# ActuatorController.net
KiCad netlist of a schematic drawn in EAGLE
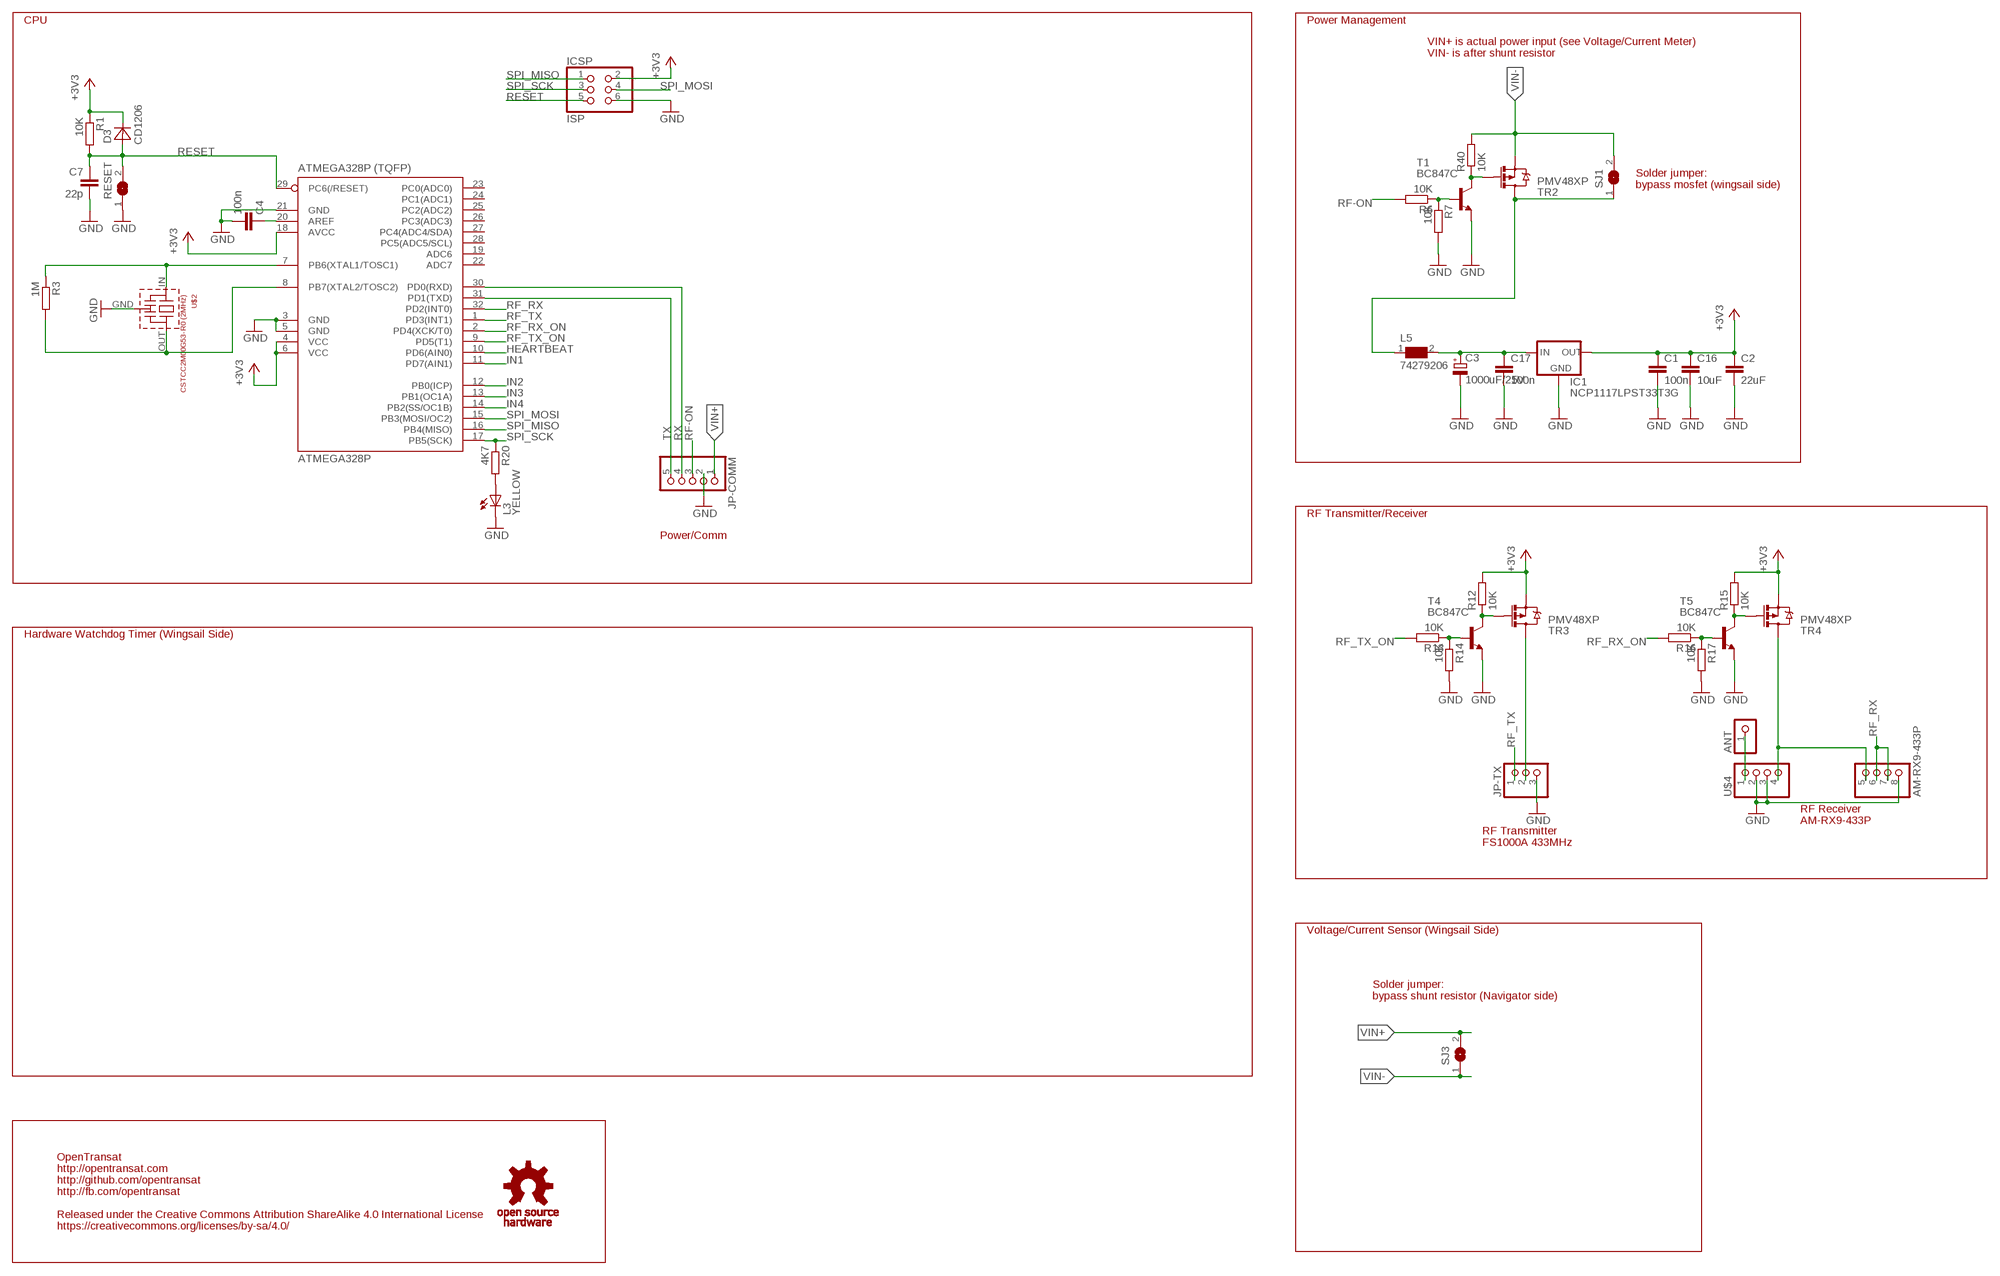
[diagram p0: schematic, sheet 1]

(export (version "E")
  (design (tool "Eeschema 10.0.6"))
  (components
    (comp (ref "ANT")
      (value "PINHD-1X1")
      (footprint "eagle-import:1X01")
      (libsource (lib "eagle-import") (part "PINHD-1X1"))
    )
    (comp (ref "ATMEGA328P")
      (value "ATMEGA328P (TQFP)")
      (footprint "eagle-import:TQFP32-08")
      (fields (field (name "MPN") "ATMEGA8-16AU"))
      (libsource (lib "eagle-import") (part "MEGA8-AI"))
    )
    (comp (ref "C1")
      (value "100n")
      (footprint "eagle-import:C0603")
      (libsource (lib "eagle-import") (part "C-EUC0603"))
    )
    (comp (ref "C2")
      (value "22uF")
      (footprint "eagle-import:C1210")
      (libsource (lib "eagle-import") (part "C-EUC1210"))
    )
    (comp (ref "C3")
      (value "1000uF/25V")
      (footprint "eagle-import:E5-10,5")
      (libsource (lib "eagle-import") (part "CPOL-EUE5-10.5"))
    )
    (comp (ref "C4")
      (value "100n")
      (footprint "eagle-import:C0603")
      (libsource (lib "eagle-import") (part "C-EUC0603"))
    )
    (comp (ref "C7")
      (value "22p")
      (footprint "eagle-import:C0603")
      (libsource (lib "eagle-import") (part "C-EUC0603"))
    )
    (comp (ref "C16")
      (value "10uF")
      (footprint "eagle-import:C1206")
      (libsource (lib "eagle-import") (part "C-EUC1206"))
    )
    (comp (ref "C17")
      (value "100n")
      (footprint "eagle-import:C0603")
      (libsource (lib "eagle-import") (part "C-EUC0603"))
    )
    (comp (ref "D3")
      (value "CD1206")
      (footprint "eagle-import:R1206")
      (libsource (lib "eagle-import") (part "CD1206"))
    )
    (comp (ref "IC1")
      (value "NCP1117LPST33T3G")
      (footprint "eagle-import:SOT223")
      (fields (field (name "MF") "Texas Instruments") (field (name "MPN") "LM1117MP-3.3"))
      (libsource (lib "eagle-import") (part "LM1117?-MP3.3"))
    )
    (comp (ref "ICSP")
      (value "ISP")
      (footprint "eagle-import:2X03")
      (libsource (lib "eagle-import") (part "PINHD-2X3"))
    )
    (comp (ref "JP-COMM")
      (value "PINHD-1X5/90")
      (footprint "eagle-import:1X05_90")
      (libsource (lib "eagle-import") (part "PINHD-1X5/90"))
    )
    (comp (ref "JP-TX")
      (value "PINHD-1X3")
      (footprint "eagle-import:1X03")
      (libsource (lib "eagle-import") (part "PINHD-1X3"))
    )
    (comp (ref "L3")
      (value "YELLOW")
      (footprint "eagle-import:CHIPLED_0805")
      (libsource (lib "eagle-import") (part "LEDCHIPLED_0805"))
    )
    (comp (ref "L5")
      (value "74279206")
      (footprint "eagle-import:0805")
      (libsource (lib "eagle-import") (part "WE-CBF_0805"))
    )
    (comp (ref "R1")
      (value "10K")
      (footprint "eagle-import:R0603")
      (libsource (lib "eagle-import") (part "R-EU_R0603"))
    )
    (comp (ref "R3")
      (value "1M")
      (footprint "eagle-import:R0603")
      (libsource (lib "eagle-import") (part "R-EU_R0603"))
    )
    (comp (ref "R6")
      (value "10K")
      (footprint "eagle-import:R0603")
      (libsource (lib "eagle-import") (part "R-EU_R0603"))
    )
    (comp (ref "R7")
      (value "10K")
      (footprint "eagle-import:R0603")
      (libsource (lib "eagle-import") (part "R-EU_R0603"))
    )
    (comp (ref "R12")
      (value "10K")
      (footprint "eagle-import:R0603")
      (libsource (lib "eagle-import") (part "R-EU_R0603"))
    )
    (comp (ref "R13")
      (value "10K")
      (footprint "eagle-import:R0603")
      (libsource (lib "eagle-import") (part "R-EU_R0603"))
    )
    (comp (ref "R14")
      (value "10K")
      (footprint "eagle-import:R0603")
      (libsource (lib "eagle-import") (part "R-EU_R0603"))
    )
    (comp (ref "R15")
      (value "10K")
      (footprint "eagle-import:R0603")
      (libsource (lib "eagle-import") (part "R-EU_R0603"))
    )
    (comp (ref "R16")
      (value "10K")
      (footprint "eagle-import:R0603")
      (libsource (lib "eagle-import") (part "R-EU_R0603"))
    )
    (comp (ref "R17")
      (value "10K")
      (footprint "eagle-import:R0603")
      (libsource (lib "eagle-import") (part "R-EU_R0603"))
    )
    (comp (ref "R20")
      (value "4K7")
      (footprint "eagle-import:R0603")
      (libsource (lib "eagle-import") (part "R-EU_R0603"))
    )
    (comp (ref "R40")
      (value "10K")
      (footprint "eagle-import:R0603")
      (libsource (lib "eagle-import") (part "R-EU_R0603"))
    )
    (comp (ref "RESET")
      (value "SJW")
      (footprint "eagle-import:SJW")
      (libsource (lib "eagle-import") (part "SJW"))
    )
    (comp (ref "SJ1") (value "SJ") (footprint "eagle-import:SJ") (libsource (lib "eagle-import") (part "SJ")))
    (comp (ref "SJ3") (value "SJ") (footprint "eagle-import:SJ") (libsource (lib "eagle-import") (part "SJ")))
    (comp (ref "T1")
      (value "BC847C")
      (footprint "eagle-import:SOT23")
      (libsource (lib "eagle-import") (part "BC847"))
    )
    (comp (ref "T4")
      (value "BC847C")
      (footprint "eagle-import:SOT23")
      (libsource (lib "eagle-import") (part "BC847"))
    )
    (comp (ref "T5")
      (value "BC847C")
      (footprint "eagle-import:SOT23")
      (libsource (lib "eagle-import") (part "BC847"))
    )
    (comp (ref "TR2")
      (value "PMV48XP")
      (footprint "eagle-import:SOT23-3")
      (libsource (lib "eagle-import") (part "MOSFET-PCHANNEL_SOT23-3"))
    )
    (comp (ref "TR3")
      (value "PMV48XP")
      (footprint "eagle-import:SOT23-3")
      (libsource (lib "eagle-import") (part "MOSFET-PCHANNEL_SOT23-3"))
    )
    (comp (ref "TR4")
      (value "PMV48XP")
      (footprint "eagle-import:SOT23-3")
      (libsource (lib "eagle-import") (part "MOSFET-PCHANNEL_SOT23-3"))
    )
    (comp (ref "U$1")
      (value "OSHW_S")
      (footprint "eagle-import:OSHWS")
      (libsource (lib "eagle-import") (part "OSHW_S"))
    )
    (comp (ref "U$2")
      (value "CSTCC2M00G53-R0 (2MHz)")
      (footprint "eagle-import:CSTCC")
      (libsource (lib "eagle-import") (part "CSTCC"))
    )
    (comp (ref "U$4")
      (value "AM-RX9-433P")
      (footprint "eagle-import:1X04")
      (libsource (lib "eagle-import") (part "AM-RX9-433P"))
    )
  )
  (nets
    (net (code "1") (name "+3V3") (class "Default")
      (node (ref "ATMEGA328P") (pin "18") (pinfunction "AVCC_18") (pintype "power_in"))
      (node (ref "ATMEGA328P") (pin "4") (pinfunction "VCC_4") (pintype "power_in"))
      (node (ref "ATMEGA328P") (pin "6") (pinfunction "VCC_6") (pintype "power_in"))
      (node (ref "C1") (pin "1") (pinfunction "1_1") (pintype "passive"))
      (node (ref "C16") (pin "1") (pinfunction "1_1") (pintype "passive"))
      (node (ref "C2") (pin "1") (pinfunction "1_1") (pintype "passive"))
      (node (ref "D3") (pin "2") (pinfunction "C_2") (pintype "passive"))
      (node (ref "IC1") (pin "2") (pinfunction "OUT_2") (pintype "passive"))
      (node (ref "IC1") (pin "4") (pinfunction "OUT_4") (pintype "passive"))
      (node (ref "ICSP") (pin "2") (pinfunction "2_2") (pintype "passive"))
      (node (ref "R1") (pin "1") (pinfunction "1_1") (pintype "passive"))
      (node (ref "R12") (pin "2") (pinfunction "2_2") (pintype "passive"))
      (node (ref "R15") (pin "2") (pinfunction "2_2") (pintype "passive"))
      (node (ref "TR3") (pin "2") (pinfunction "S_2") (pintype "passive"))
      (node (ref "TR4") (pin "2") (pinfunction "S_2") (pintype "passive"))
    )
    (net (code "2") (name "/HEARTBEAT") (class "Default")
      (node (ref "ATMEGA328P") (pin "10") (pinfunction "PD6(AIN0)_10") (pintype "bidirectional"))
    )
    (net (code "3") (name "/IN1") (class "Default")
      (node (ref "ATMEGA328P") (pin "11") (pinfunction "PD7(AIN1)_11") (pintype "bidirectional"))
    )
    (net (code "4") (name "/IN2") (class "Default")
      (node (ref "ATMEGA328P") (pin "12") (pinfunction "PB0(ICP)_12") (pintype "bidirectional"))
    )
    (net (code "5") (name "/IN3") (class "Default")
      (node (ref "ATMEGA328P") (pin "13") (pinfunction "PB1(OC1A)_13") (pintype "bidirectional"))
    )
    (net (code "6") (name "/IN4") (class "Default")
      (node (ref "ATMEGA328P") (pin "14") (pinfunction "PB2(SS/OC1B)_14") (pintype "bidirectional"))
    )
    (net (code "7") (name "/RESET") (class "Default")
      (node (ref "ATMEGA328P") (pin "29") (pinfunction "PC6(/RESET)_29") (pintype "bidirectional"))
      (node (ref "C7") (pin "1") (pinfunction "1_1") (pintype "passive"))
      (node (ref "D3") (pin "1") (pinfunction "A_1") (pintype "passive"))
      (node (ref "ICSP") (pin "5") (pinfunction "5_5") (pintype "passive"))
      (node (ref "R1") (pin "2") (pinfunction "2_2") (pintype "passive"))
      (node (ref "RESET") (pin "2") (pinfunction "2_2") (pintype "passive"))
    )
    (net (code "8") (name "/RF-ON") (class "Default")
      (node (ref "JP-COMM") (pin "3") (pinfunction "3_3") (pintype "passive"))
      (node (ref "R6") (pin "2") (pinfunction "2_2") (pintype "passive"))
    )
    (net (code "9") (name "/RF_RX") (class "Default")
      (node (ref "ATMEGA328P") (pin "32") (pinfunction "PD2(INT0)_32") (pintype "bidirectional"))
      (node (ref "U$4") (pin "6") (pinfunction "6_6") (pintype "passive"))
      (node (ref "U$4") (pin "7") (pinfunction "7_7") (pintype "passive"))
    )
    (net (code "10") (name "/RF_RX_ON") (class "Default")
      (node (ref "ATMEGA328P") (pin "2") (pinfunction "PD4(XCK/T0)_2") (pintype "bidirectional"))
      (node (ref "R16") (pin "2") (pinfunction "2_2") (pintype "passive"))
    )
    (net (code "11") (name "/RF_TX") (class "Default")
      (node (ref "ATMEGA328P") (pin "1") (pinfunction "PD3(INT1)_1") (pintype "bidirectional"))
      (node (ref "JP-TX") (pin "1") (pinfunction "1_1") (pintype "passive"))
    )
    (net (code "12") (name "/RF_TX_ON") (class "Default")
      (node (ref "ATMEGA328P") (pin "9") (pinfunction "PD5(T1)_9") (pintype "bidirectional"))
      (node (ref "R13") (pin "2") (pinfunction "2_2") (pintype "passive"))
    )
    (net (code "13") (name "/RX") (class "Default")
      (node (ref "ATMEGA328P") (pin "30") (pinfunction "PD0(RXD)_30") (pintype "bidirectional"))
      (node (ref "JP-COMM") (pin "4") (pinfunction "4_4") (pintype "passive"))
    )
    (net (code "14") (name "/SPI_MISO") (class "Default")
      (node (ref "ATMEGA328P") (pin "16") (pinfunction "PB4(MISO)_16") (pintype "bidirectional"))
      (node (ref "ICSP") (pin "1") (pinfunction "1_1") (pintype "passive"))
    )
    (net (code "15") (name "/SPI_MOSI") (class "Default")
      (node (ref "ATMEGA328P") (pin "15") (pinfunction "PB3(MOSI/OC2)_15") (pintype "bidirectional"))
      (node (ref "ICSP") (pin "4") (pinfunction "4_4") (pintype "passive"))
    )
    (net (code "16") (name "/SPI_SCK") (class "Default")
      (node (ref "ATMEGA328P") (pin "17") (pinfunction "PB5(SCK)_17") (pintype "bidirectional"))
      (node (ref "ICSP") (pin "3") (pinfunction "3_3") (pintype "passive"))
      (node (ref "R20") (pin "1") (pinfunction "1_1") (pintype "passive"))
    )
    (net (code "17") (name "/TX") (class "Default")
      (node (ref "ATMEGA328P") (pin "31") (pinfunction "PD1(TXD)_31") (pintype "bidirectional"))
      (node (ref "JP-COMM") (pin "5") (pinfunction "5_5") (pintype "passive"))
    )
    (net (code "18") (name "GND") (class "Default")
      (node (ref "ATMEGA328P") (pin "21") (pinfunction "GND_21") (pintype "power_in"))
      (node (ref "ATMEGA328P") (pin "3") (pinfunction "GND_3") (pintype "power_in"))
      (node (ref "ATMEGA328P") (pin "5") (pinfunction "GND_5") (pintype "power_in"))
      (node (ref "C1") (pin "2") (pinfunction "2_2") (pintype "passive"))
      (node (ref "C16") (pin "2") (pinfunction "2_2") (pintype "passive"))
      (node (ref "C17") (pin "2") (pinfunction "2_2") (pintype "passive"))
      (node (ref "C2") (pin "2") (pinfunction "2_2") (pintype "passive"))
      (node (ref "C3") (pin "-") (pinfunction "-_-") (pintype "passive"))
      (node (ref "C4") (pin "2") (pinfunction "2_2") (pintype "passive"))
      (node (ref "C7") (pin "2") (pinfunction "2_2") (pintype "passive"))
      (node (ref "IC1") (pin "1") (pinfunction "GND_1") (pintype "input"))
      (node (ref "ICSP") (pin "6") (pinfunction "6_6") (pintype "passive"))
      (node (ref "JP-COMM") (pin "2") (pinfunction "2_2") (pintype "passive"))
      (node (ref "JP-TX") (pin "3") (pinfunction "3_3") (pintype "passive"))
      (node (ref "L3") (pin "C") (pinfunction "C_C") (pintype "passive"))
      (node (ref "R14") (pin "2") (pinfunction "2_2") (pintype "passive"))
      (node (ref "R17") (pin "2") (pinfunction "2_2") (pintype "passive"))
      (node (ref "R7") (pin "2") (pinfunction "2_2") (pintype "passive"))
      (node (ref "RESET") (pin "1") (pinfunction "1_1") (pintype "passive"))
      (node (ref "T1") (pin "2") (pinfunction "E_2") (pintype "passive"))
      (node (ref "T4") (pin "2") (pinfunction "E_2") (pintype "passive"))
      (node (ref "T5") (pin "2") (pinfunction "E_2") (pintype "passive"))
      (node (ref "U$2") (pin "GND") (pinfunction "GND_GND") (pintype "power_in"))
      (node (ref "U$4") (pin "2") (pinfunction "2_2") (pintype "passive"))
      (node (ref "U$4") (pin "3") (pinfunction "3_3") (pintype "passive"))
      (node (ref "U$4") (pin "8") (pinfunction "8_8") (pintype "passive"))
    )
    (net (code "19") (name "Net-(ANT-Pad1)") (class "Default")
      (node (ref "ANT") (pin "1") (pinfunction "1_1") (pintype "passive"))
      (node (ref "U$4") (pin "1") (pinfunction "1_1") (pintype "passive"))
    )
    (net (code "20") (name "Net-(ATMEGA328P-AREF)") (class "Default")
      (node (ref "ATMEGA328P") (pin "20") (pinfunction "AREF_20") (pintype "passive"))
      (node (ref "C4") (pin "1") (pinfunction "1_1") (pintype "passive"))
    )
    (net (code "21") (name "Net-(ATMEGA328P-PB6(XTAL1{slash}TOSC1))") (class "Default")
      (node (ref "ATMEGA328P") (pin "7") (pinfunction "PB6(XTAL1/TOSC1)_7") (pintype "bidirectional"))
      (node (ref "R3") (pin "1") (pinfunction "1_1") (pintype "passive"))
      (node (ref "U$2") (pin "IN") (pinfunction "IN_IN") (pintype "input"))
    )
    (net (code "22") (name "Net-(ATMEGA328P-PB7(XTAL2{slash}TOSC2))") (class "Default")
      (node (ref "ATMEGA328P") (pin "8") (pinfunction "PB7(XTAL2/TOSC2)_8") (pintype "bidirectional"))
      (node (ref "R3") (pin "2") (pinfunction "2_2") (pintype "passive"))
      (node (ref "U$2") (pin "OUT") (pinfunction "OUT_OUT") (pintype "output"))
    )
    (net (code "23") (name "Net-(IC1-IN)") (class "Default")
      (node (ref "C17") (pin "1") (pinfunction "1_1") (pintype "passive"))
      (node (ref "C3") (pin "+") (pinfunction "+_+") (pintype "passive"))
      (node (ref "IC1") (pin "3") (pinfunction "IN_3") (pintype "input"))
      (node (ref "L5") (pin "2") (pinfunction "2_2") (pintype "passive"))
    )
    (net (code "24") (name "Net-(L3-PadA)") (class "Default")
      (node (ref "L3") (pin "A") (pinfunction "A_A") (pintype "passive"))
      (node (ref "R20") (pin "2") (pinfunction "2_2") (pintype "passive"))
    )
    (net (code "25") (name "Net-(T1-B)") (class "Default")
      (node (ref "R6") (pin "1") (pinfunction "1_1") (pintype "passive"))
      (node (ref "R7") (pin "1") (pinfunction "1_1") (pintype "passive"))
      (node (ref "T1") (pin "1") (pinfunction "B_1") (pintype "passive"))
    )
    (net (code "26") (name "Net-(T1-C)") (class "Default")
      (node (ref "R40") (pin "1") (pinfunction "1_1") (pintype "passive"))
      (node (ref "T1") (pin "3") (pinfunction "C_3") (pintype "passive"))
      (node (ref "TR2") (pin "1") (pinfunction "G_1") (pintype "passive"))
    )
    (net (code "27") (name "Net-(T4-B)") (class "Default")
      (node (ref "R13") (pin "1") (pinfunction "1_1") (pintype "passive"))
      (node (ref "R14") (pin "1") (pinfunction "1_1") (pintype "passive"))
      (node (ref "T4") (pin "1") (pinfunction "B_1") (pintype "passive"))
    )
    (net (code "28") (name "Net-(T4-C)") (class "Default")
      (node (ref "R12") (pin "1") (pinfunction "1_1") (pintype "passive"))
      (node (ref "T4") (pin "3") (pinfunction "C_3") (pintype "passive"))
      (node (ref "TR3") (pin "1") (pinfunction "G_1") (pintype "passive"))
    )
    (net (code "29") (name "Net-(T5-B)") (class "Default")
      (node (ref "R16") (pin "1") (pinfunction "1_1") (pintype "passive"))
      (node (ref "R17") (pin "1") (pinfunction "1_1") (pintype "passive"))
      (node (ref "T5") (pin "1") (pinfunction "B_1") (pintype "passive"))
    )
    (net (code "30") (name "Net-(T5-C)") (class "Default")
      (node (ref "R15") (pin "1") (pinfunction "1_1") (pintype "passive"))
      (node (ref "T5") (pin "3") (pinfunction "C_3") (pintype "passive"))
      (node (ref "TR4") (pin "1") (pinfunction "G_1") (pintype "passive"))
    )
    (net (code "31") (name "Net-(TR2-D)") (class "Default")
      (node (ref "L5") (pin "1") (pinfunction "1_1") (pintype "passive"))
      (node (ref "SJ1") (pin "1") (pinfunction "1_1") (pintype "passive"))
      (node (ref "TR2") (pin "3") (pinfunction "D_3") (pintype "passive"))
    )
    (net (code "32") (name "Net-(TR3-D)") (class "Default")
      (node (ref "JP-TX") (pin "2") (pinfunction "2_2") (pintype "passive"))
      (node (ref "TR3") (pin "3") (pinfunction "D_3") (pintype "passive"))
    )
    (net (code "33") (name "Net-(TR4-D)") (class "Default")
      (node (ref "TR4") (pin "3") (pinfunction "D_3") (pintype "passive"))
      (node (ref "U$4") (pin "4") (pinfunction "4_4") (pintype "passive"))
      (node (ref "U$4") (pin "5") (pinfunction "5_5") (pintype "passive"))
    )
    (net (code "34") (name "VIN+") (class "Default")
      (node (ref "JP-COMM") (pin "1") (pinfunction "1_1") (pintype "passive"))
      (node (ref "SJ3") (pin "2") (pinfunction "2_2") (pintype "passive"))
    )
    (net (code "35") (name "VIN-") (class "Default")
      (node (ref "R40") (pin "2") (pinfunction "2_2") (pintype "passive"))
      (node (ref "SJ1") (pin "2") (pinfunction "2_2") (pintype "passive"))
      (node (ref "SJ3") (pin "1") (pinfunction "1_1") (pintype "passive"))
      (node (ref "TR2") (pin "2") (pinfunction "S_2") (pintype "passive"))
    )
    (net (code "36") (name "unconnected-(ATMEGA328P-ADC6-Pad19)") (class "Default")
      (node (ref "ATMEGA328P") (pin "19") (pinfunction "ADC6_19") (pintype "bidirectional"))
    )
    (net (code "37") (name "unconnected-(ATMEGA328P-ADC7-Pad22)") (class "Default")
      (node (ref "ATMEGA328P") (pin "22") (pinfunction "ADC7_22") (pintype "bidirectional"))
    )
    (net (code "38") (name "unconnected-(ATMEGA328P-PC0(ADC0)-Pad23)") (class "Default")
      (node (ref "ATMEGA328P") (pin "23") (pinfunction "PC0(ADC0)_23") (pintype "bidirectional"))
    )
    (net (code "39") (name "unconnected-(ATMEGA328P-PC1(ADC1)-Pad24)") (class "Default")
      (node (ref "ATMEGA328P") (pin "24") (pinfunction "PC1(ADC1)_24") (pintype "bidirectional"))
    )
    (net (code "40") (name "unconnected-(ATMEGA328P-PC2(ADC2)-Pad25)") (class "Default")
      (node (ref "ATMEGA328P") (pin "25") (pinfunction "PC2(ADC2)_25") (pintype "bidirectional"))
    )
    (net (code "41") (name "unconnected-(ATMEGA328P-PC3(ADC3)-Pad26)") (class "Default")
      (node (ref "ATMEGA328P") (pin "26") (pinfunction "PC3(ADC3)_26") (pintype "bidirectional"))
    )
    (net (code "42") (name "unconnected-(ATMEGA328P-PC4(ADC4{slash}SDA)-Pad27)") (class "Default")
      (node (ref "ATMEGA328P") (pin "27") (pinfunction "PC4(ADC4/SDA)_27") (pintype "bidirectional"))
    )
    (net (code "43") (name "unconnected-(ATMEGA328P-PC5(ADC5{slash}SCL)-Pad28)") (class "Default")
      (node (ref "ATMEGA328P") (pin "28") (pinfunction "PC5(ADC5/SCL)_28") (pintype "bidirectional"))
    )
  )
)
